# altimeter_new.net
KiCad netlist of a schematic drawn in EAGLE
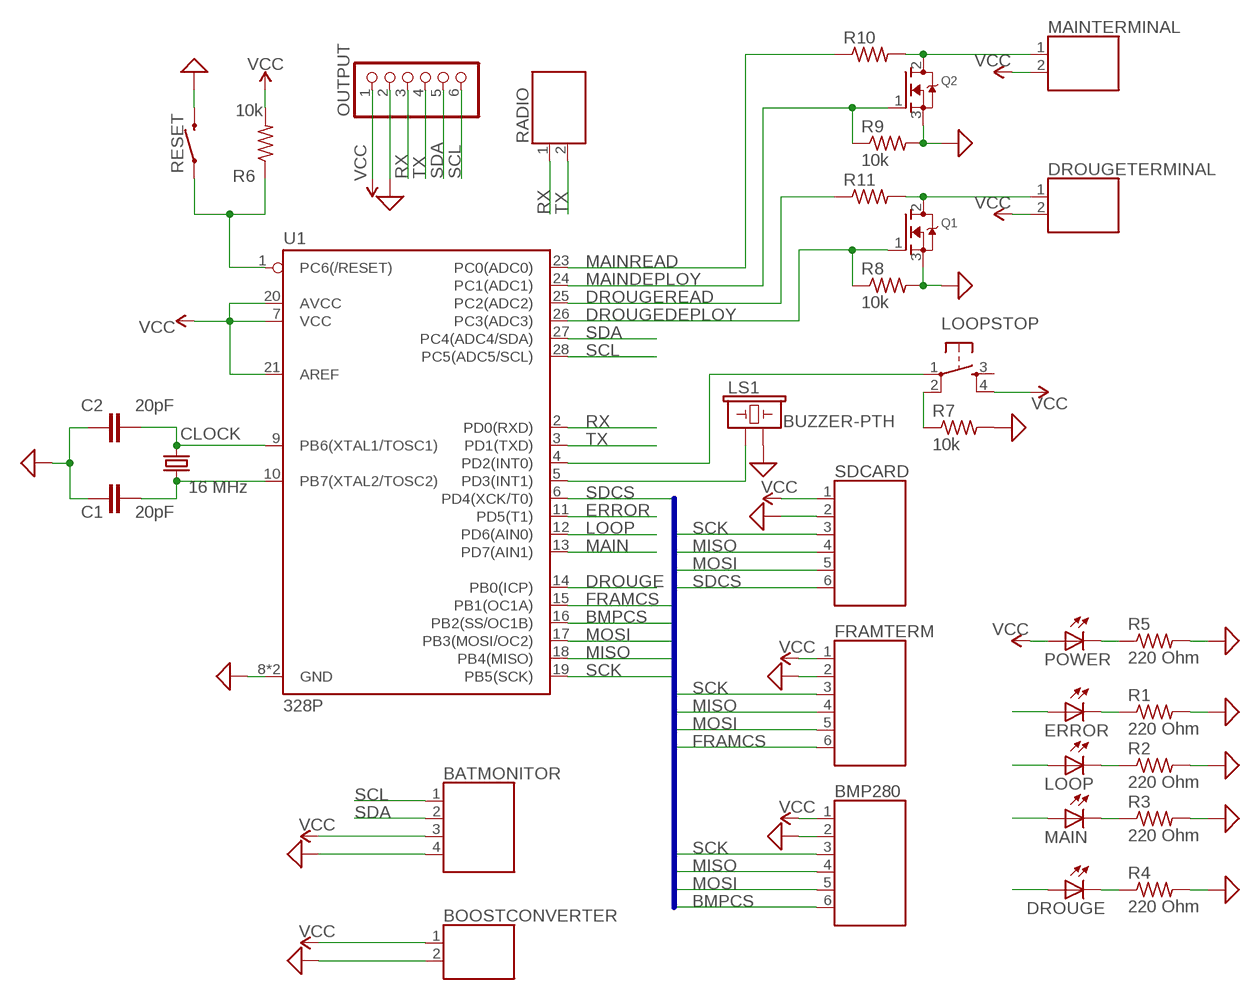
[diagram p0: schematic, sheet 1]

(export (version "E")
  (design (tool "Eeschema 10.0.6"))
  (components
    (comp (ref "BATMONITOR")
      (value "691386700004")
      (footprint "eagle-import:691386700004")
      (libsource (lib "eagle-import") (part "691386700004"))
    )
    (comp (ref "BMP280")
      (value "691386700006")
      (footprint "eagle-import:691386700006")
      (libsource (lib "eagle-import") (part "691386700006"))
    )
    (comp (ref "BOOSTCONVERTER")
      (value "691386700002")
      (footprint "eagle-import:691386700002")
      (libsource (lib "eagle-import") (part "691386700002"))
    )
    (comp (ref "C1")
      (value "20pF")
      (footprint "eagle-import:CAP-PTH-2.54")
      (fields (field (name "SPICEPREFIX") "C"))
      (libsource (lib "eagle-import") (part "22PF-PTH-2.54MM-200V-5%"))
    )
    (comp (ref "C2")
      (value "20pF")
      (footprint "eagle-import:CAP-PTH-2.54")
      (fields (field (name "SPICEPREFIX") "C"))
      (libsource (lib "eagle-import") (part "22PF-PTH-2.54MM-200V-5%"))
    )
    (comp (ref "CLOCK")
      (value "16 MHz")
      (footprint "eagle-import:HC49U-V")
      (fields (field (name "SPICEPREFIX") "C"))
      (libsource (lib "eagle-import") (part "CRYSTALHC49U-V"))
    )
    (comp (ref "DROUGE")
      (value "LED5MM")
      (footprint "eagle-import:LED5MM")
      (libsource (lib "eagle-import") (part "LED5MM"))
    )
    (comp (ref "DROUGETERMINAL")
      (value "691386700002")
      (footprint "eagle-import:691386700002")
      (libsource (lib "eagle-import") (part "691386700002"))
    )
    (comp (ref "ERROR")
      (value "LED5MM")
      (footprint "eagle-import:LED5MM")
      (libsource (lib "eagle-import") (part "LED5MM"))
    )
    (comp (ref "FRAMTERM")
      (value "691386700006")
      (footprint "eagle-import:691386700006")
      (libsource (lib "eagle-import") (part "691386700006"))
    )
    (comp (ref "LOOP")
      (value "LED5MM")
      (footprint "eagle-import:LED5MM")
      (libsource (lib "eagle-import") (part "LED5MM"))
    )
    (comp (ref "LOOPSTOP")
      (value "TAC_SWITCHPTH")
      (footprint "eagle-import:TACTILE-PTH")
      (libsource (lib "eagle-import") (part "TAC_SWITCHPTH"))
    )
    (comp (ref "LS1")
      (value "BUZZER-PTH")
      (footprint "eagle-import:BUZZER-12MM")
      (libsource (lib "eagle-import") (part "BUZZER-PTH"))
    )
    (comp (ref "MAIN")
      (value "LED5MM")
      (footprint "eagle-import:LED5MM")
      (libsource (lib "eagle-import") (part "LED5MM"))
    )
    (comp (ref "MAINTERMINAL")
      (value "691386700002")
      (footprint "eagle-import:691386700002")
      (libsource (lib "eagle-import") (part "691386700002"))
    )
    (comp (ref "OUTPUT")
      (value "PINHD-1X6")
      (footprint "eagle-import:1X06")
      (libsource (lib "eagle-import") (part "PINHD-1X6"))
    )
    (comp (ref "POWER")
      (value "LED5MM")
      (footprint "eagle-import:LED5MM")
      (libsource (lib "eagle-import") (part "LED5MM"))
    )
    (comp (ref "Q1")
      (value "MOSFET-NGDS_TO220V")
      (footprint "eagle-import:TO220V")
      (libsource (lib "eagle-import") (part "MOSFET-NGDS_TO220V"))
    )
    (comp (ref "Q2")
      (value "MOSFET-NGDS_TO220V")
      (footprint "eagle-import:TO220V")
      (libsource (lib "eagle-import") (part "MOSFET-NGDS_TO220V"))
    )
    (comp (ref "R1")
      (value "220 Ohm")
      (footprint "eagle-import:0204_7")
      (libsource (lib "eagle-import") (part "R-US_0204/7"))
    )
    (comp (ref "R2")
      (value "220 Ohm")
      (footprint "eagle-import:0204_7")
      (libsource (lib "eagle-import") (part "R-US_0204/7"))
    )
    (comp (ref "R3")
      (value "220 Ohm")
      (footprint "eagle-import:0204_7")
      (libsource (lib "eagle-import") (part "R-US_0204/7"))
    )
    (comp (ref "R4")
      (value "220 Ohm")
      (footprint "eagle-import:0204_7")
      (libsource (lib "eagle-import") (part "R-US_0204/7"))
    )
    (comp (ref "R5")
      (value "220 Ohm")
      (footprint "eagle-import:0204_7")
      (libsource (lib "eagle-import") (part "R-US_0204/7"))
    )
    (comp (ref "R6")
      (value "10k")
      (footprint "eagle-import:0204_7")
      (libsource (lib "eagle-import") (part "R-US_0204/7"))
    )
    (comp (ref "R7")
      (value "10k")
      (footprint "eagle-import:0204_7")
      (libsource (lib "eagle-import") (part "R-US_0204/7"))
    )
    (comp (ref "R8")
      (value "10k")
      (footprint "eagle-import:0204_7")
      (libsource (lib "eagle-import") (part "R-US_0204/7"))
    )
    (comp (ref "R9")
      (value "10k")
      (footprint "eagle-import:0204_7")
      (libsource (lib "eagle-import") (part "R-US_0204/7"))
    )
    (comp (ref "R10")
      (value "R-US_0204/7")
      (footprint "eagle-import:0204_7")
      (libsource (lib "eagle-import") (part "R-US_0204/7"))
    )
    (comp (ref "R11")
      (value "R-US_0204/7")
      (footprint "eagle-import:0204_7")
      (libsource (lib "eagle-import") (part "R-US_0204/7"))
    )
    (comp (ref "RADIO")
      (value "691386700002")
      (footprint "eagle-import:691386700002")
      (libsource (lib "eagle-import") (part "691386700002"))
    )
    (comp (ref "RESET")
      (value "MOMENTARY-SWITCH-SPST-PTH-6.0MM")
      (footprint "eagle-import:TACTILE_SWITCH_PTH_6.0MM")
      (libsource (lib "eagle-import") (part "MOMENTARY-SWITCH-SPST-PTH-6.0MM"))
    )
    (comp (ref "SDCARD")
      (value "691386700006")
      (footprint "eagle-import:691386700006")
      (libsource (lib "eagle-import") (part "691386700006"))
    )
    (comp (ref "U1")
      (value "328P")
      (footprint "eagle-import:DIP28")
      (libsource (lib "eagle-import") (part "ATMEGA328P_PDIP"))
    )
  )
  (nets
    (net (code "1") (name "/BMPCS") (class "Default")
      (node (ref "BMP280") (pin "6") (pinfunction "6_6") (pintype "passive"))
      (node (ref "U1") (pin "16") (pinfunction "PB2(SS/OC1B)_16") (pintype "bidirectional"))
    )
    (net (code "2") (name "/DROUGE") (class "Default")
      (node (ref "DROUGE") (pin "A") (pinfunction "A_A") (pintype "passive"))
      (node (ref "U1") (pin "14") (pinfunction "PB0(ICP)_14") (pintype "bidirectional"))
    )
    (net (code "3") (name "/DROUGEDEPLOY") (class "Default")
      (node (ref "Q1") (pin "1") (pinfunction "G_1") (pintype "bidirectional"))
      (node (ref "R8") (pin "1") (pinfunction "1_1") (pintype "passive"))
      (node (ref "U1") (pin "26") (pinfunction "PC3(ADC3)_26") (pintype "bidirectional"))
    )
    (net (code "4") (name "/DROUGEREAD") (class "Default")
      (node (ref "R11") (pin "1") (pinfunction "1_1") (pintype "passive"))
      (node (ref "U1") (pin "25") (pinfunction "PC2(ADC2)_25") (pintype "bidirectional"))
    )
    (net (code "5") (name "/ERROR") (class "Default")
      (node (ref "ERROR") (pin "A") (pinfunction "A_A") (pintype "passive"))
      (node (ref "U1") (pin "11") (pinfunction "PD5(T1)_11") (pintype "bidirectional"))
    )
    (net (code "6") (name "/FRAMCS") (class "Default")
      (node (ref "FRAMTERM") (pin "6") (pinfunction "6_6") (pintype "passive"))
      (node (ref "U1") (pin "15") (pinfunction "PB1(OC1A)_15") (pintype "bidirectional"))
    )
    (net (code "7") (name "/LOOP") (class "Default")
      (node (ref "LOOP") (pin "A") (pinfunction "A_A") (pintype "passive"))
      (node (ref "U1") (pin "12") (pinfunction "PD6(AIN0)_12") (pintype "bidirectional"))
    )
    (net (code "8") (name "/MAIN") (class "Default")
      (node (ref "MAIN") (pin "A") (pinfunction "A_A") (pintype "passive"))
      (node (ref "U1") (pin "13") (pinfunction "PD7(AIN1)_13") (pintype "bidirectional"))
    )
    (net (code "9") (name "/MAINDEPLOY") (class "Default")
      (node (ref "Q2") (pin "1") (pinfunction "G_1") (pintype "bidirectional"))
      (node (ref "R9") (pin "1") (pinfunction "1_1") (pintype "passive"))
      (node (ref "U1") (pin "24") (pinfunction "PC1(ADC1)_24") (pintype "bidirectional"))
    )
    (net (code "10") (name "/MAINREAD") (class "Default")
      (node (ref "R10") (pin "1") (pinfunction "1_1") (pintype "passive"))
      (node (ref "U1") (pin "23") (pinfunction "PC0(ADC0)_23") (pintype "bidirectional"))
    )
    (net (code "11") (name "/MISO") (class "Default")
      (node (ref "BMP280") (pin "4") (pinfunction "4_4") (pintype "passive"))
      (node (ref "FRAMTERM") (pin "4") (pinfunction "4_4") (pintype "passive"))
      (node (ref "SDCARD") (pin "4") (pinfunction "4_4") (pintype "passive"))
      (node (ref "U1") (pin "18") (pinfunction "PB4(MISO)_18") (pintype "bidirectional"))
    )
    (net (code "12") (name "/MOSI") (class "Default")
      (node (ref "BMP280") (pin "5") (pinfunction "5_5") (pintype "passive"))
      (node (ref "FRAMTERM") (pin "5") (pinfunction "5_5") (pintype "passive"))
      (node (ref "SDCARD") (pin "5") (pinfunction "5_5") (pintype "passive"))
      (node (ref "U1") (pin "17") (pinfunction "PB3(MOSI/OC2)_17") (pintype "bidirectional"))
    )
    (net (code "13") (name "/RX") (class "Default")
      (node (ref "OUTPUT") (pin "3") (pinfunction "3_3") (pintype "passive"))
      (node (ref "RADIO") (pin "1") (pinfunction "1_1") (pintype "passive"))
      (node (ref "U1") (pin "2") (pinfunction "PD0(RXD)_2") (pintype "bidirectional"))
    )
    (net (code "14") (name "/SCK") (class "Default")
      (node (ref "BMP280") (pin "3") (pinfunction "3_3") (pintype "passive"))
      (node (ref "FRAMTERM") (pin "3") (pinfunction "3_3") (pintype "passive"))
      (node (ref "SDCARD") (pin "3") (pinfunction "3_3") (pintype "passive"))
      (node (ref "U1") (pin "19") (pinfunction "PB5(SCK)_19") (pintype "bidirectional"))
    )
    (net (code "15") (name "/SCL") (class "Default")
      (node (ref "BATMONITOR") (pin "1") (pinfunction "1_1") (pintype "passive"))
      (node (ref "OUTPUT") (pin "6") (pinfunction "6_6") (pintype "passive"))
      (node (ref "U1") (pin "28") (pinfunction "PC5(ADC5/SCL)_28") (pintype "bidirectional"))
    )
    (net (code "16") (name "/SDA") (class "Default")
      (node (ref "BATMONITOR") (pin "2") (pinfunction "2_2") (pintype "passive"))
      (node (ref "OUTPUT") (pin "5") (pinfunction "5_5") (pintype "passive"))
      (node (ref "U1") (pin "27") (pinfunction "PC4(ADC4/SDA)_27") (pintype "bidirectional"))
    )
    (net (code "17") (name "/SDCS") (class "Default")
      (node (ref "SDCARD") (pin "6") (pinfunction "6_6") (pintype "passive"))
      (node (ref "U1") (pin "6") (pinfunction "PD4(XCK/T0)_6") (pintype "bidirectional"))
    )
    (net (code "18") (name "/TX") (class "Default")
      (node (ref "OUTPUT") (pin "4") (pinfunction "4_4") (pintype "passive"))
      (node (ref "RADIO") (pin "2") (pinfunction "2_2") (pintype "passive"))
      (node (ref "U1") (pin "3") (pinfunction "PD1(TXD)_3") (pintype "bidirectional"))
    )
    (net (code "19") (name "Net-(DROUGE-C)") (class "Default")
      (node (ref "DROUGE") (pin "K") (pinfunction "C_K") (pintype "passive"))
      (node (ref "R4") (pin "1") (pinfunction "1_1") (pintype "passive"))
    )
    (net (code "20") (name "Net-(ERROR-C)") (class "Default")
      (node (ref "ERROR") (pin "K") (pinfunction "C_K") (pintype "passive"))
      (node (ref "R1") (pin "1") (pinfunction "1_1") (pintype "passive"))
    )
    (net (code "21") (name "Net-(LOOP-C)") (class "Default")
      (node (ref "LOOP") (pin "K") (pinfunction "C_K") (pintype "passive"))
      (node (ref "R2") (pin "1") (pinfunction "1_1") (pintype "passive"))
    )
    (net (code "22") (name "Net-(LOOPSTOP-Pad2)") (class "Default")
      (node (ref "LOOPSTOP") (pin "2") (pinfunction "2_2") (pintype "passive"))
      (node (ref "R7") (pin "1") (pinfunction "1_1") (pintype "passive"))
    )
    (net (code "23") (name "Net-(LS1-1)") (class "Default")
      (node (ref "LS1") (pin "+") (pinfunction "1_+") (pintype "passive"))
      (node (ref "U1") (pin "5") (pinfunction "PD3(INT1)_5") (pintype "bidirectional"))
    )
    (net (code "24") (name "Net-(MAIN-C)") (class "Default")
      (node (ref "MAIN") (pin "K") (pinfunction "C_K") (pintype "passive"))
      (node (ref "R3") (pin "1") (pinfunction "1_1") (pintype "passive"))
    )
    (net (code "25") (name "Net-(POWER-C)") (class "Default")
      (node (ref "POWER") (pin "K") (pinfunction "C_K") (pintype "passive"))
      (node (ref "R5") (pin "1") (pinfunction "1_1") (pintype "passive"))
    )
    (net (code "26") (name "Net-(Q1-D)") (class "Default")
      (node (ref "DROUGETERMINAL") (pin "1") (pinfunction "1_1") (pintype "passive"))
      (node (ref "Q1") (pin "2") (pinfunction "D_2") (pintype "bidirectional"))
      (node (ref "R11") (pin "2") (pinfunction "2_2") (pintype "passive"))
    )
    (net (code "27") (name "Net-(Q2-D)") (class "Default")
      (node (ref "MAINTERMINAL") (pin "1") (pinfunction "1_1") (pintype "passive"))
      (node (ref "Q2") (pin "2") (pinfunction "D_2") (pintype "bidirectional"))
      (node (ref "R10") (pin "2") (pinfunction "2_2") (pintype "passive"))
    )
    (net (code "28") (name "Net-(U1-PB6(XTAL1{slash}TOSC1))") (class "Default")
      (node (ref "C2") (pin "2") (pinfunction "2_2") (pintype "passive"))
      (node (ref "CLOCK") (pin "2") (pinfunction "2_2") (pintype "passive"))
      (node (ref "U1") (pin "9") (pinfunction "PB6(XTAL1/TOSC1)_9") (pintype "bidirectional"))
    )
    (net (code "29") (name "Net-(U1-PB7(XTAL2{slash}TOSC2))") (class "Default")
      (node (ref "C1") (pin "2") (pinfunction "2_2") (pintype "passive"))
      (node (ref "CLOCK") (pin "1") (pinfunction "1_1") (pintype "passive"))
      (node (ref "U1") (pin "10") (pinfunction "PB7(XTAL2/TOSC2)_10") (pintype "bidirectional"))
    )
    (net (code "30") (name "Net-(U1-PC6({slash}RESET))") (class "Default")
      (node (ref "R6") (pin "1") (pinfunction "1_1") (pintype "passive"))
      (node (ref "RESET") (pin "1") (pinfunction "1_1") (pintype "passive"))
      (node (ref "U1") (pin "1") (pinfunction "PC6(/RESET)_1") (pintype "bidirectional"))
    )
    (net (code "31") (name "Net-(U1-PD2(INT0))") (class "Default")
      (node (ref "LOOPSTOP") (pin "1") (pinfunction "1_1") (pintype "passive"))
      (node (ref "U1") (pin "4") (pinfunction "PD2(INT0)_4") (pintype "bidirectional"))
    )
    (net (code "32") (name "SUP") (class "Default")
      (node (ref "BATMONITOR") (pin "4") (pinfunction "4_4") (pintype "passive"))
      (node (ref "BMP280") (pin "2") (pinfunction "2_2") (pintype "passive"))
      (node (ref "BOOSTCONVERTER") (pin "2") (pinfunction "2_2") (pintype "passive"))
      (node (ref "C1") (pin "1") (pinfunction "1_1") (pintype "passive"))
      (node (ref "C2") (pin "1") (pinfunction "1_1") (pintype "passive"))
      (node (ref "FRAMTERM") (pin "2") (pinfunction "2_2") (pintype "passive"))
      (node (ref "LS1") (pin "-") (pinfunction "2_-") (pintype "passive"))
      (node (ref "OUTPUT") (pin "2") (pinfunction "2_2") (pintype "passive"))
      (node (ref "Q1") (pin "3") (pinfunction "S_3") (pintype "bidirectional"))
      (node (ref "Q2") (pin "3") (pinfunction "S_3") (pintype "bidirectional"))
      (node (ref "R1") (pin "2") (pinfunction "2_2") (pintype "passive"))
      (node (ref "R2") (pin "2") (pinfunction "2_2") (pintype "passive"))
      (node (ref "R3") (pin "2") (pinfunction "2_2") (pintype "passive"))
      (node (ref "R4") (pin "2") (pinfunction "2_2") (pintype "passive"))
      (node (ref "R5") (pin "2") (pinfunction "2_2") (pintype "passive"))
      (node (ref "R7") (pin "2") (pinfunction "2_2") (pintype "passive"))
      (node (ref "R8") (pin "2") (pinfunction "2_2") (pintype "passive"))
      (node (ref "R9") (pin "2") (pinfunction "2_2") (pintype "passive"))
      (node (ref "RESET") (pin "3") (pinfunction "2_3") (pintype "passive"))
      (node (ref "SDCARD") (pin "2") (pinfunction "2_2") (pintype "passive"))
      (node (ref "U1") (pin "22") (pinfunction "GND_22") (pintype "bidirectional"))
      (node (ref "U1") (pin "8") (pinfunction "GND_8") (pintype "bidirectional"))
    )
    (net (code "33") (name "VCC") (class "Default")
      (node (ref "BATMONITOR") (pin "3") (pinfunction "3_3") (pintype "passive"))
      (node (ref "BMP280") (pin "1") (pinfunction "1_1") (pintype "passive"))
      (node (ref "BOOSTCONVERTER") (pin "1") (pinfunction "1_1") (pintype "passive"))
      (node (ref "DROUGETERMINAL") (pin "2") (pinfunction "2_2") (pintype "passive"))
      (node (ref "FRAMTERM") (pin "1") (pinfunction "1_1") (pintype "passive"))
      (node (ref "LOOPSTOP") (pin "4") (pinfunction "4_4") (pintype "passive"))
      (node (ref "MAINTERMINAL") (pin "2") (pinfunction "2_2") (pintype "passive"))
      (node (ref "OUTPUT") (pin "1") (pinfunction "1_1") (pintype "passive"))
      (node (ref "POWER") (pin "A") (pinfunction "A_A") (pintype "passive"))
      (node (ref "R6") (pin "2") (pinfunction "2_2") (pintype "passive"))
      (node (ref "SDCARD") (pin "1") (pinfunction "1_1") (pintype "passive"))
      (node (ref "U1") (pin "20") (pinfunction "AVCC_20") (pintype "bidirectional"))
      (node (ref "U1") (pin "21") (pinfunction "AREF_21") (pintype "bidirectional"))
      (node (ref "U1") (pin "7") (pinfunction "VCC_7") (pintype "bidirectional"))
    )
    (net (code "34") (name "unconnected-(LOOPSTOP-Pad3)") (class "Default")
      (node (ref "LOOPSTOP") (pin "3") (pinfunction "3_3") (pintype "passive"))
    )
  )
)
